# mainMARLIN.net
KiCad netlist of a schematic drawn in Altium Designer
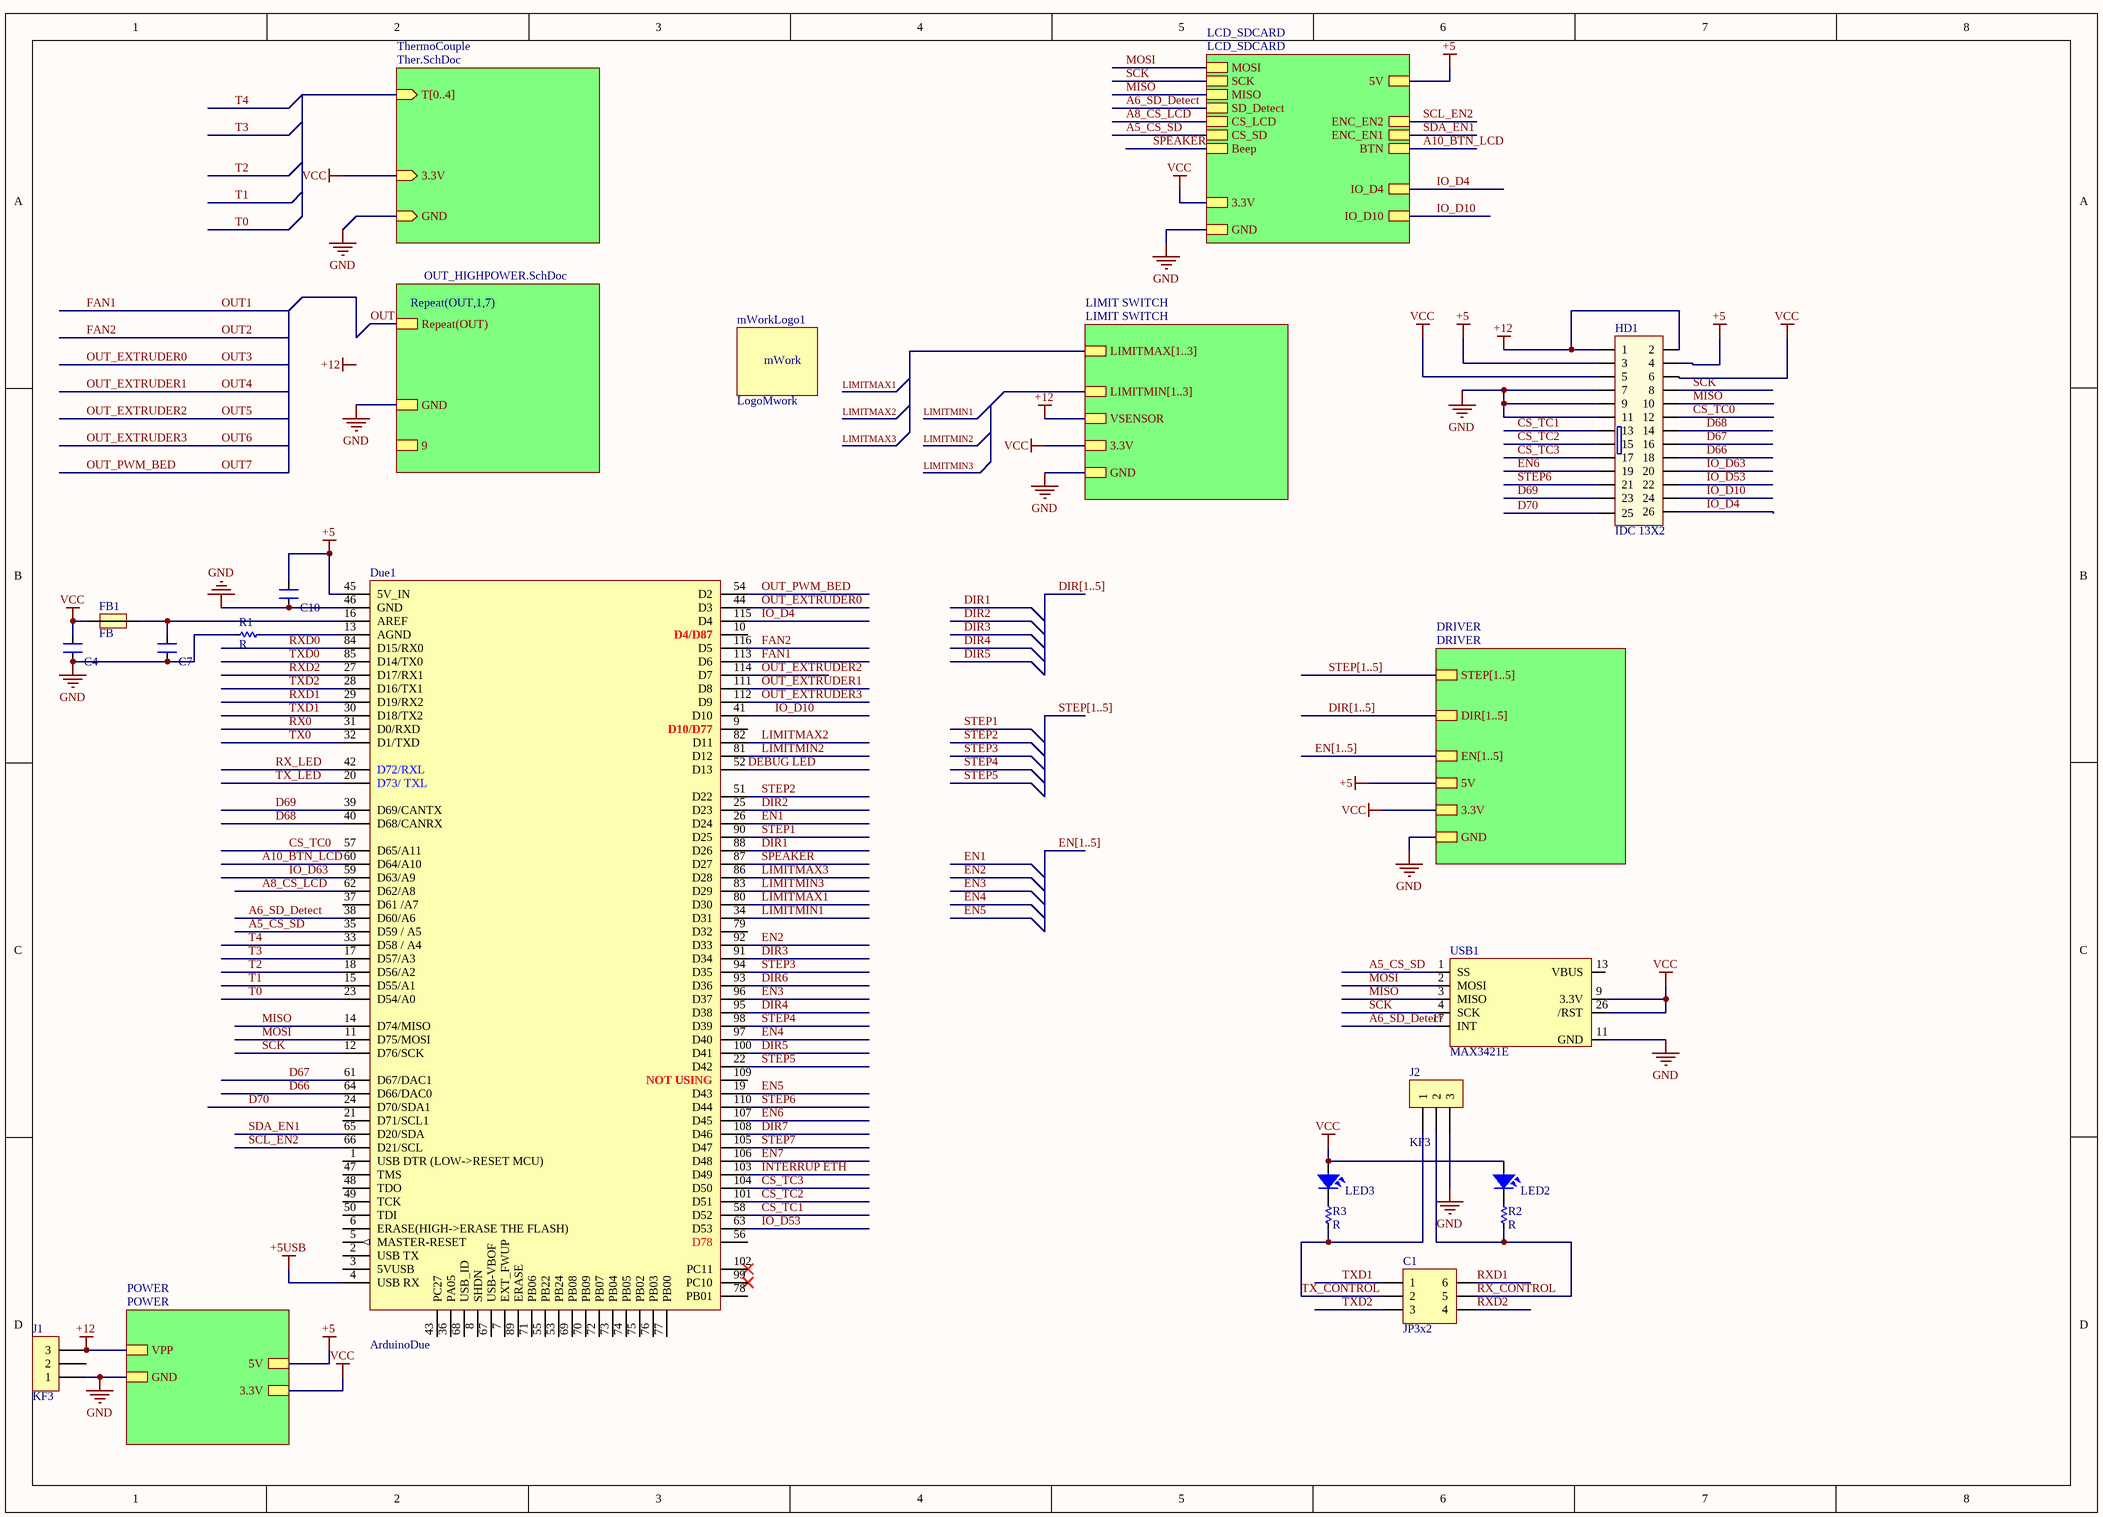
[diagram p0: mainMARLIN.SchDoc]

(export (version "E")
  (design (tool "Eeschema 10.0.6"))
  (components
    (comp (ref "C1")
      (value "JP3x2")
      (footprint "JP3-D2T")
      (description "WR-PHD 2.54 mm Dual Socket Header")
      (fields
        (field (name "MANUFACTURER") "Würth Elektronik eiSos GmbH")
        (field (name "PARTNO") "61300621821")
        (field (name "CREATED BY") "Karrer Zheng")
      )
      (libsource (lib "LIBRARY") (part "JP3x2"))
    )
    (comp (ref "C4") (value "CN") (footprint "CN-SMD-0603_big") (libsource (lib "nhan") (part "CN")))
    (comp (ref "C7") (value "CN") (footprint "CN-SMD-0603_big") (libsource (lib "nhan") (part "CN")))
    (comp (ref "C10") (value "CN") (footprint "CN-SMD-0603_big") (libsource (lib "nhan") (part "CN")))
    (comp (ref "Due1")
      (value "ArduinoDue")
      (footprint "DUE_MODULE_SMT")
      (libsource (lib "nhan") (part "ArduinoDue"))
    )
    (comp (ref "FB1") (value "FB") (footprint "Capacitor_805") (libsource (lib "nhan") (part "FB")))
    (comp (ref "HD1")
      (value "IDC 13X2")
      (footprint "IDC26-B")
      (description "IDC 13x2")
      (libsource (lib "BanLinhKien") (part "IDC 13X2"))
    )
    (comp (ref "J1")
      (value "KF3")
      (footprint "KF3-5.08T")
      (fields
        (field (name "MANUFACTURER") "Würth Elektronik eiSos GmbH")
        (field (name "PARTNO") "691103110003")
        (field (name "CREATED BY") "Karrer Zheng")
      )
      (libsource (lib "BanLinhKien") (part "KF3"))
    )
    (comp (ref "J2")
      (value "KF3")
      (footprint "KF3-5.08T")
      (fields
        (field (name "MANUFACTURER") "Würth Elektronik eiSos GmbH")
        (field (name "PARTNO") "691103110003")
        (field (name "CREATED BY") "Karrer Zheng")
      )
      (libsource (lib "LIBRARY") (part "KF3"))
    )
    (comp (ref "LED2") (value "LED") (footprint "LED-0805-Blue") (libsource (lib "LIBRARY") (part "LED SMD")))
    (comp (ref "LED3") (value "LED") (footprint "LED-0805-Blue") (libsource (lib "LIBRARY") (part "LED SMD")))
    (comp (ref "mWorkLogo1")
      (value "LogoMwork")
      (footprint "LogoMwork15*6")
      (libsource (lib "nhan") (part "LogoMwork"))
    )
    (comp (ref "R1") (value "R") (footprint "RES-SMD-0603_BIG") (libsource (lib "nhan") (part "R")))
    (comp (ref "R2") (value "R") (footprint "RES-SMD-0603_BIG") (libsource (lib "nhan") (part "R")))
    (comp (ref "R3") (value "R") (footprint "RES-SMD-0603_BIG") (libsource (lib "nhan") (part "R")))
    (comp (ref "USB1")
      (value "MAX3421E")
      (footprint "USB_SHIELD")
      (libsource (lib "nhan") (part "USB_Shield_MAX3421E"))
    )
  )
  (nets
    (net (code "1") (name "+5") (class "Default")
      (node (ref "C10") (pin "2") (pinfunction "2_2") (pintype "passive"))
      (node (ref "Due1") (pin "45") (pinfunction "5V_IN_45") (pintype "passive"))
      (node (ref "HD1") (pin "3") (pinfunction "3_3") (pintype "passive"))
      (node (ref "HD1") (pin "4") (pinfunction "4_4") (pintype "passive"))
    )
    (net (code "2") (name "+5USB") (class "Default")
      (node (ref "Due1") (pin "4") (pinfunction "USB_RX_4") (pintype "passive"))
    )
    (net (code "3") (name "+12") (class "Default")
      (node (ref "HD1") (pin "1") (pinfunction "1_1") (pintype "passive"))
      (node (ref "HD1") (pin "2") (pinfunction "2_2") (pintype "passive"))
      (node (ref "J1") (pin "3") (pinfunction "3_3") (pintype "passive"))
    )
    (net (code "5") (name "/A5_CS_SD") (class "Default")
      (node (ref "Due1") (pin "35") (pinfunction "D59_/_A5_35") (pintype "passive"))
      (node (ref "USB1") (pin "1") (pinfunction "SS_1") (pintype "passive"))
    )
    (net (code "6") (name "/A6_SD_Detect") (class "Default")
      (node (ref "Due1") (pin "38") (pinfunction "D60/A6_38") (pintype "passive"))
      (node (ref "USB1") (pin "17") (pinfunction "INT_17") (pintype "passive"))
    )
    (net (code "7") (name "/A8_CS_LCD") (class "Default")
      (node (ref "Due1") (pin "62") (pinfunction "D62/A8_62") (pintype "passive"))
    )
    (net (code "8") (name "/A10_BTN_LCD") (class "Default")
      (node (ref "Due1") (pin "60") (pinfunction "D64/A10_60") (pintype "passive"))
    )
    (net (code "9") (name "/CS_TC0") (class "Default")
      (node (ref "Due1") (pin "57") (pinfunction "D65/A11_57") (pintype "passive"))
      (node (ref "HD1") (pin "12") (pinfunction "12_12") (pintype "passive"))
    )
    (net (code "10") (name "/CS_TC1") (class "Default")
      (node (ref "Due1") (pin "58") (pinfunction "D52_58") (pintype "passive"))
      (node (ref "HD1") (pin "13") (pinfunction "13_13") (pintype "passive"))
    )
    (net (code "11") (name "/CS_TC2") (class "Default")
      (node (ref "Due1") (pin "101") (pinfunction "D51_101") (pintype "passive"))
      (node (ref "HD1") (pin "15") (pinfunction "15_15") (pintype "passive"))
    )
    (net (code "12") (name "/CS_TC3") (class "Default")
      (node (ref "Due1") (pin "104") (pinfunction "D50_104") (pintype "passive"))
      (node (ref "HD1") (pin "17") (pinfunction "17_17") (pintype "passive"))
    )
    (net (code "13") (name "/D66") (class "Default")
      (node (ref "Due1") (pin "64") (pinfunction "D66/DAC0_64") (pintype "passive"))
      (node (ref "HD1") (pin "18") (pinfunction "18_18") (pintype "passive"))
    )
    (net (code "14") (name "/D67") (class "Default")
      (node (ref "Due1") (pin "61") (pinfunction "D67/DAC1_61") (pintype "passive"))
      (node (ref "HD1") (pin "16") (pinfunction "16_16") (pintype "passive"))
    )
    (net (code "15") (name "/D68") (class "Default")
      (node (ref "Due1") (pin "40") (pinfunction "D68/CANRX_40") (pintype "passive"))
      (node (ref "HD1") (pin "14") (pinfunction "14_14") (pintype "passive"))
    )
    (net (code "16") (name "/D69") (class "Default")
      (node (ref "Due1") (pin "39") (pinfunction "D69/CANTX_39") (pintype "passive"))
      (node (ref "HD1") (pin "23") (pinfunction "23_23") (pintype "passive"))
    )
    (net (code "17") (name "/D70") (class "Default")
      (node (ref "Due1") (pin "24") (pinfunction "D70/SDA1_24") (pintype "passive"))
      (node (ref "HD1") (pin "25") (pinfunction "25_25") (pintype "passive"))
    )
    (net (code "18") (name "/DEBUG LED") (class "Default")
      (node (ref "Due1") (pin "52") (pinfunction "D13_52") (pintype "passive"))
    )
    (net (code "19") (name "/DIR1") (class "Default")
      (node (ref "Due1") (pin "88") (pinfunction "D26_88") (pintype "passive"))
    )
    (net (code "20") (name "/DIR2") (class "Default")
      (node (ref "Due1") (pin "25") (pinfunction "D23_25") (pintype "passive"))
    )
    (net (code "21") (name "/DIR3") (class "Default")
      (node (ref "Due1") (pin "91") (pinfunction "D34_91") (pintype "passive"))
    )
    (net (code "22") (name "/DIR4") (class "Default")
      (node (ref "Due1") (pin "95") (pinfunction "D38_95") (pintype "passive"))
    )
    (net (code "23") (name "/DIR5") (class "Default")
      (node (ref "Due1") (pin "100") (pinfunction "D41_100") (pintype "passive"))
    )
    (net (code "24") (name "/DIR6") (class "Default")
      (node (ref "Due1") (pin "93") (pinfunction "D36_93") (pintype "passive"))
    )
    (net (code "25") (name "/DIR7") (class "Default")
      (node (ref "Due1") (pin "108") (pinfunction "D46_108") (pintype "passive"))
    )
    (net (code "27") (name "/EN1") (class "Default")
      (node (ref "Due1") (pin "26") (pinfunction "D24_26") (pintype "passive"))
    )
    (net (code "28") (name "/EN2") (class "Default")
      (node (ref "Due1") (pin "92") (pinfunction "D33_92") (pintype "passive"))
    )
    (net (code "29") (name "/EN3") (class "Default")
      (node (ref "Due1") (pin "96") (pinfunction "D37_96") (pintype "passive"))
    )
    (net (code "30") (name "/EN4") (class "Default")
      (node (ref "Due1") (pin "97") (pinfunction "D40_97") (pintype "passive"))
    )
    (net (code "31") (name "/EN5") (class "Default")
      (node (ref "Due1") (pin "19") (pinfunction "D43_19") (pintype "passive"))
    )
    (net (code "32") (name "/EN6") (class "Default")
      (node (ref "Due1") (pin "107") (pinfunction "D45_107") (pintype "passive"))
      (node (ref "HD1") (pin "19") (pinfunction "19_19") (pintype "passive"))
    )
    (net (code "33") (name "/EN7") (class "Default")
      (node (ref "Due1") (pin "106") (pinfunction "D48_106") (pintype "passive"))
    )
    (net (code "35") (name "/FAN1") (class "Default")
      (node (ref "Due1") (pin "113") (pinfunction "D6_113") (pintype "passive"))
    )
    (net (code "36") (name "/FAN2") (class "Default")
      (node (ref "Due1") (pin "116") (pinfunction "D5_116") (pintype "passive"))
    )
    (net (code "37") (name "/INTERRUP ETH") (class "Default")
      (node (ref "Due1") (pin "103") (pinfunction "D49_103") (pintype "passive"))
    )
    (net (code "38") (name "/IO_D4") (class "Default")
      (node (ref "Due1") (pin "115") (pinfunction "D4_115") (pintype "passive"))
      (node (ref "HD1") (pin "26") (pinfunction "26_26") (pintype "passive"))
    )
    (net (code "39") (name "/IO_D10") (class "Default")
      (node (ref "Due1") (pin "41") (pinfunction "D10_41") (pintype "passive"))
      (node (ref "HD1") (pin "24") (pinfunction "24_24") (pintype "passive"))
    )
    (net (code "40") (name "/IO_D53") (class "Default")
      (node (ref "Due1") (pin "63") (pinfunction "D53_63") (pintype "passive"))
      (node (ref "HD1") (pin "22") (pinfunction "22_22") (pintype "passive"))
    )
    (net (code "41") (name "/IO_D63") (class "Default")
      (node (ref "Due1") (pin "59") (pinfunction "D63/A9_59") (pintype "passive"))
      (node (ref "HD1") (pin "20") (pinfunction "20_20") (pintype "passive"))
    )
    (net (code "42") (name "/LIMITMAX1") (class "Default")
      (node (ref "Due1") (pin "80") (pinfunction "D30_80") (pintype "passive"))
    )
    (net (code "43") (name "/LIMITMAX2") (class "Default")
      (node (ref "Due1") (pin "82") (pinfunction "D11_82") (pintype "passive"))
    )
    (net (code "44") (name "/LIMITMAX3") (class "Default")
      (node (ref "Due1") (pin "86") (pinfunction "D28_86") (pintype "passive"))
    )
    (net (code "46") (name "/LIMITMIN1") (class "Default")
      (node (ref "Due1") (pin "34") (pinfunction "D31_34") (pintype "passive"))
    )
    (net (code "47") (name "/LIMITMIN2") (class "Default")
      (node (ref "Due1") (pin "81") (pinfunction "D12_81") (pintype "passive"))
    )
    (net (code "48") (name "/LIMITMIN3") (class "Default")
      (node (ref "Due1") (pin "83") (pinfunction "D29_83") (pintype "passive"))
    )
    (net (code "50") (name "/MISO") (class "Default")
      (node (ref "Due1") (pin "14") (pinfunction "D74/MISO_14") (pintype "passive"))
      (node (ref "HD1") (pin "10") (pinfunction "10_10") (pintype "passive"))
      (node (ref "USB1") (pin "3") (pinfunction "MISO_3") (pintype "passive"))
    )
    (net (code "51") (name "/MOSI") (class "Default")
      (node (ref "Due1") (pin "11") (pinfunction "D75/MOSI_11") (pintype "passive"))
      (node (ref "USB1") (pin "2") (pinfunction "MOSI_2") (pintype "passive"))
    )
    (net (code "53") (name "/OUT3") (class "Default")
      (node (ref "Due1") (pin "44") (pinfunction "D3_44") (pintype "passive"))
    )
    (net (code "54") (name "/OUT4") (class "Default")
      (node (ref "Due1") (pin "111") (pinfunction "D8_111") (pintype "passive"))
    )
    (net (code "55") (name "/OUT5") (class "Default")
      (node (ref "Due1") (pin "114") (pinfunction "D7_114") (pintype "passive"))
    )
    (net (code "56") (name "/OUT6") (class "Default")
      (node (ref "Due1") (pin "112") (pinfunction "D9_112") (pintype "passive"))
    )
    (net (code "57") (name "/OUT7") (class "Default")
      (node (ref "Due1") (pin "54") (pinfunction "D2_54") (pintype "passive"))
    )
    (net (code "58") (name "/RX0") (class "Default")
      (node (ref "Due1") (pin "31") (pinfunction "D0/RXD_31") (pintype "passive"))
    )
    (net (code "59") (name "/RXD0") (class "Default")
      (node (ref "Due1") (pin "84") (pinfunction "D15/RX0_84") (pintype "passive"))
    )
    (net (code "60") (name "/RXD1") (class "Default")
      (node (ref "C1") (pin "6") (pinfunction "6_6") (pintype "passive"))
      (node (ref "Due1") (pin "29") (pinfunction "D19/RX2_29") (pintype "passive"))
    )
    (net (code "61") (name "/RXD2") (class "Default")
      (node (ref "C1") (pin "4") (pinfunction "4_4") (pintype "passive"))
      (node (ref "Due1") (pin "27") (pinfunction "D17/RX1_27") (pintype "passive"))
    )
    (net (code "62") (name "/RX_CONTROL") (class "Default")
      (node (ref "C1") (pin "5") (pinfunction "5_5") (pintype "passive"))
      (node (ref "J2") (pin "2") (pinfunction "2_2") (pintype "passive"))
      (node (ref "R2") (pin "1") (pinfunction "1_1") (pintype "passive"))
    )
    (net (code "63") (name "/RX_LED") (class "Default")
      (node (ref "Due1") (pin "42") (pinfunction "D72/RXL_42") (pintype "passive"))
    )
    (net (code "64") (name "/SCK") (class "Default")
      (node (ref "Due1") (pin "12") (pinfunction "D76/SCK_12") (pintype "passive"))
      (node (ref "HD1") (pin "8") (pinfunction "8_8") (pintype "passive"))
      (node (ref "USB1") (pin "4") (pinfunction "SCK_4") (pintype "passive"))
    )
    (net (code "65") (name "/SCL_EN2") (class "Default")
      (node (ref "Due1") (pin "66") (pinfunction "D21/SCL_66") (pintype "passive"))
    )
    (net (code "66") (name "/SDA_EN1") (class "Default")
      (node (ref "Due1") (pin "65") (pinfunction "D20/SDA_65") (pintype "passive"))
    )
    (net (code "67") (name "/SPEAKER") (class "Default")
      (node (ref "Due1") (pin "87") (pinfunction "D27_87") (pintype "passive"))
    )
    (net (code "68") (name "/STEP1") (class "Default")
      (node (ref "Due1") (pin "90") (pinfunction "D25_90") (pintype "passive"))
    )
    (net (code "69") (name "/STEP2") (class "Default")
      (node (ref "Due1") (pin "51") (pinfunction "D22_51") (pintype "passive"))
    )
    (net (code "70") (name "/STEP3") (class "Default")
      (node (ref "Due1") (pin "94") (pinfunction "D35_94") (pintype "passive"))
    )
    (net (code "71") (name "/STEP4") (class "Default")
      (node (ref "Due1") (pin "98") (pinfunction "D39_98") (pintype "passive"))
    )
    (net (code "72") (name "/STEP5") (class "Default")
      (node (ref "Due1") (pin "22") (pinfunction "D42_22") (pintype "passive"))
    )
    (net (code "73") (name "/STEP6") (class "Default")
      (node (ref "Due1") (pin "110") (pinfunction "D44_110") (pintype "passive"))
      (node (ref "HD1") (pin "21") (pinfunction "21_21") (pintype "passive"))
    )
    (net (code "74") (name "/STEP7") (class "Default")
      (node (ref "Due1") (pin "105") (pinfunction "D47_105") (pintype "passive"))
    )
    (net (code "76") (name "/T0") (class "Default")
      (node (ref "Due1") (pin "23") (pinfunction "D54/A0_23") (pintype "passive"))
    )
    (net (code "77") (name "/T1") (class "Default")
      (node (ref "Due1") (pin "15") (pinfunction "D55/A1_15") (pintype "passive"))
    )
    (net (code "78") (name "/T2") (class "Default")
      (node (ref "Due1") (pin "18") (pinfunction "D56/A2_18") (pintype "passive"))
    )
    (net (code "79") (name "/T3") (class "Default")
      (node (ref "Due1") (pin "17") (pinfunction "D57/A3_17") (pintype "passive"))
    )
    (net (code "80") (name "/T4") (class "Default")
      (node (ref "Due1") (pin "33") (pinfunction "D58_/_A4_33") (pintype "passive"))
    )
    (net (code "81") (name "/TX0") (class "Default")
      (node (ref "Due1") (pin "32") (pinfunction "D1/TXD_32") (pintype "passive"))
    )
    (net (code "82") (name "/TXD0") (class "Default")
      (node (ref "Due1") (pin "85") (pinfunction "D14/TX0_85") (pintype "passive"))
    )
    (net (code "83") (name "/TXD1") (class "Default")
      (node (ref "C1") (pin "1") (pinfunction "1_1") (pintype "passive"))
      (node (ref "Due1") (pin "30") (pinfunction "D18/TX2_30") (pintype "passive"))
    )
    (net (code "84") (name "/TXD2") (class "Default")
      (node (ref "C1") (pin "3") (pinfunction "3_3") (pintype "passive"))
      (node (ref "Due1") (pin "28") (pinfunction "D16/TX1_28") (pintype "passive"))
    )
    (net (code "85") (name "/TX_CONTROL") (class "Default")
      (node (ref "C1") (pin "2") (pinfunction "2_2") (pintype "passive"))
      (node (ref "J2") (pin "1") (pinfunction "1_1") (pintype "passive"))
      (node (ref "R3") (pin "1") (pinfunction "1_1") (pintype "passive"))
    )
    (net (code "86") (name "/TX_LED") (class "Default")
      (node (ref "Due1") (pin "20") (pinfunction "D73/_TXL_20") (pintype "passive"))
    )
    (net (code "88") (name "GND") (class "Default")
      (node (ref "C10") (pin "1") (pinfunction "1_1") (pintype "passive"))
      (node (ref "C4") (pin "1") (pinfunction "1_1") (pintype "passive"))
      (node (ref "C7") (pin "1") (pinfunction "1_1") (pintype "passive"))
      (node (ref "Due1") (pin "46") (pinfunction "GND_46") (pintype "passive"))
      (node (ref "HD1") (pin "11") (pinfunction "11_11") (pintype "passive"))
      (node (ref "HD1") (pin "7") (pinfunction "7_7") (pintype "passive"))
      (node (ref "HD1") (pin "9") (pinfunction "9_9") (pintype "passive"))
      (node (ref "J1") (pin "1") (pinfunction "1_1") (pintype "passive"))
      (node (ref "J2") (pin "3") (pinfunction "3_3") (pintype "passive"))
      (node (ref "R1") (pin "2") (pinfunction "2_2") (pintype "passive"))
      (node (ref "USB1") (pin "11") (pinfunction "GND_11") (pintype "passive"))
    )
    (net (code "89") (name "Net-(Due1-AGND)") (class "Default")
      (node (ref "Due1") (pin "13") (pinfunction "AGND_13") (pintype "passive"))
      (node (ref "R1") (pin "1") (pinfunction "1_1") (pintype "passive"))
    )
    (net (code "90") (name "Net-(Due1-AREF)") (class "Default")
      (node (ref "C7") (pin "2") (pinfunction "2_2") (pintype "passive"))
      (node (ref "Due1") (pin "16") (pinfunction "AREF_16") (pintype "passive"))
      (node (ref "FB1") (pin "2") (pinfunction "2_2") (pintype "passive"))
    )
    (net (code "91") (name "Net-(LED2-Pad2)") (class "Default")
      (node (ref "LED2") (pin "2") (pinfunction "2_2") (pintype "passive"))
      (node (ref "R2") (pin "2") (pinfunction "2_2") (pintype "passive"))
    )
    (net (code "92") (name "Net-(LED3-Pad2)") (class "Default")
      (node (ref "LED3") (pin "2") (pinfunction "2_2") (pintype "passive"))
      (node (ref "R3") (pin "2") (pinfunction "2_2") (pintype "passive"))
    )
    (net (code "93") (name "VCC") (class "Default")
      (node (ref "C4") (pin "2") (pinfunction "2_2") (pintype "passive"))
      (node (ref "FB1") (pin "1") (pinfunction "1_1") (pintype "passive"))
      (node (ref "HD1") (pin "5") (pinfunction "5_5") (pintype "passive"))
      (node (ref "HD1") (pin "6") (pinfunction "6_6") (pintype "passive"))
      (node (ref "LED2") (pin "1") (pinfunction "1_1") (pintype "passive"))
      (node (ref "LED3") (pin "1") (pinfunction "1_1") (pintype "passive"))
      (node (ref "USB1") (pin "26") (pinfunction "/RST_26") (pintype "passive"))
      (node (ref "USB1") (pin "9") (pinfunction "3.3V_9") (pintype "passive"))
    )
    (net (code "94") (name "unconnected-(Due1-5VUSB-Pad3)") (class "Default")
      (node (ref "Due1") (pin "3") (pinfunction "5VUSB_3") (pintype "passive"))
    )
    (net (code "95") (name "unconnected-(Due1-D4{slash}D87-Pad10)") (class "Default")
      (node (ref "Due1") (pin "10") (pinfunction "D4/D87_10") (pintype "passive"))
    )
    (net (code "96") (name "unconnected-(Due1-D10{slash}D77-Pad9)") (class "Default")
      (node (ref "Due1") (pin "9") (pinfunction "D10/D77_9") (pintype "passive"))
    )
    (net (code "97") (name "unconnected-(Due1-D32-Pad79)") (class "Default")
      (node (ref "Due1") (pin "79") (pinfunction "D32_79") (pintype "passive"))
    )
    (net (code "98") (name "unconnected-(Due1-D61_{slash}A7-Pad37)") (class "Default")
      (node (ref "Due1") (pin "37") (pinfunction "D61_/A7_37") (pintype "passive"))
    )
    (net (code "99") (name "unconnected-(Due1-D71{slash}SCL1-Pad21)") (class "Default")
      (node (ref "Due1") (pin "21") (pinfunction "D71/SCL1_21") (pintype "passive"))
    )
    (net (code "100") (name "unconnected-(Due1-D78-Pad56)") (class "Default")
      (node (ref "Due1") (pin "56") (pinfunction "D78_56") (pintype "passive"))
    )
    (net (code "101") (name "unconnected-(Due1-ERASE(HIGH->ERASE_THE_FLASH)-Pad6)") (class "Default")
      (node (ref "Due1") (pin "6") (pinfunction "ERASE(HIGH->ERASE_THE_FLASH)_6") (pintype "passive"))
    )
    (net (code "102") (name "unconnected-(Due1-ERASE-Pad89)") (class "Default")
      (node (ref "Due1") (pin "89") (pinfunction "ERASE_89") (pintype "passive"))
    )
    (net (code "103") (name "unconnected-(Due1-EXT_FWUP-Pad7)") (class "Default")
      (node (ref "Due1") (pin "7") (pinfunction "EXT_FWUP_7") (pintype "passive"))
    )
    (net (code "104") (name "unconnected-(Due1-MASTER-RESET-Pad5)") (class "Default")
      (node (ref "Due1") (pin "5") (pinfunction "MASTER-RESET_5") (pintype "output"))
    )
    (net (code "105") (name "unconnected-(Due1-NOT_USING-Pad109)") (class "Default")
      (node (ref "Due1") (pin "109") (pinfunction "NOT_USING_109") (pintype "passive"))
    )
    (net (code "106") (name "unconnected-(Due1-PA05-Pad36)") (class "Default")
      (node (ref "Due1") (pin "36") (pinfunction "PA05_36") (pintype "passive"))
    )
    (net (code "107") (name "unconnected-(Due1-PB00-Pad77)") (class "Default")
      (node (ref "Due1") (pin "77") (pinfunction "PB00_77") (pintype "passive"))
    )
    (net (code "108") (name "unconnected-(Due1-PB01-Pad78)") (class "Default")
      (node (ref "Due1") (pin "78") (pinfunction "PB01_78") (pintype "passive"))
    )
    (net (code "109") (name "unconnected-(Due1-PB02-Pad75)") (class "Default")
      (node (ref "Due1") (pin "75") (pinfunction "PB02_75") (pintype "passive"))
    )
    (net (code "110") (name "unconnected-(Due1-PB03-Pad76)") (class "Default")
      (node (ref "Due1") (pin "76") (pinfunction "PB03_76") (pintype "passive"))
    )
    (net (code "111") (name "unconnected-(Due1-PB04-Pad73)") (class "Default")
      (node (ref "Due1") (pin "73") (pinfunction "PB04_73") (pintype "passive"))
    )
    (net (code "112") (name "unconnected-(Due1-PB05-Pad74)") (class "Default")
      (node (ref "Due1") (pin "74") (pinfunction "PB05_74") (pintype "passive"))
    )
    (net (code "113") (name "unconnected-(Due1-PB06-Pad71)") (class "Default")
      (node (ref "Due1") (pin "71") (pinfunction "PB06_71") (pintype "passive"))
    )
    (net (code "114") (name "unconnected-(Due1-PB07-Pad72)") (class "Default")
      (node (ref "Due1") (pin "72") (pinfunction "PB07_72") (pintype "passive"))
    )
    (net (code "115") (name "unconnected-(Due1-PB08-Pad69)") (class "Default")
      (node (ref "Due1") (pin "69") (pinfunction "PB08_69") (pintype "passive"))
    )
    (net (code "116") (name "unconnected-(Due1-PB09-Pad70)") (class "Default")
      (node (ref "Due1") (pin "70") (pinfunction "PB09_70") (pintype "passive"))
    )
    (net (code "117") (name "unconnected-(Due1-PB22-Pad55)") (class "Default")
      (node (ref "Due1") (pin "55") (pinfunction "PB22_55") (pintype "passive"))
    )
    (net (code "118") (name "unconnected-(Due1-PB24-Pad53)") (class "Default")
      (node (ref "Due1") (pin "53") (pinfunction "PB24_53") (pintype "passive"))
    )
    (net (code "119") (name "unconnected-(Due1-PC10-Pad99)") (class "Default")
      (node (ref "Due1") (pin "99") (pinfunction "PC10_99") (pintype "passive+no_connect"))
    )
    (net (code "120") (name "unconnected-(Due1-PC11-Pad102)") (class "Default")
      (node (ref "Due1") (pin "102") (pinfunction "PC11_102") (pintype "passive+no_connect"))
    )
    (net (code "121") (name "unconnected-(Due1-PC27-Pad43)") (class "Default")
      (node (ref "Due1") (pin "43") (pinfunction "PC27_43") (pintype "passive"))
    )
    (net (code "122") (name "unconnected-(Due1-SHDN-Pad8)") (class "Default")
      (node (ref "Due1") (pin "8") (pinfunction "SHDN_8") (pintype "passive"))
    )
    (net (code "123") (name "unconnected-(Due1-TCK-Pad49)") (class "Default")
      (node (ref "Due1") (pin "49") (pinfunction "TCK_49") (pintype "passive"))
    )
    (net (code "124") (name "unconnected-(Due1-TDI-Pad50)") (class "Default")
      (node (ref "Due1") (pin "50") (pinfunction "TDI_50") (pintype "passive"))
    )
    (net (code "125") (name "unconnected-(Due1-TDO-Pad48)") (class "Default")
      (node (ref "Due1") (pin "48") (pinfunction "TDO_48") (pintype "passive"))
    )
    (net (code "126") (name "unconnected-(Due1-TMS-Pad47)") (class "Default")
      (node (ref "Due1") (pin "47") (pinfunction "TMS_47") (pintype "passive"))
    )
    (net (code "127") (name "unconnected-(Due1-USB-VBOF-Pad67)") (class "Default")
      (node (ref "Due1") (pin "67") (pinfunction "USB-VBOF_67") (pintype "passive"))
    )
    (net (code "128") (name "unconnected-(Due1-USB_DTR_(LOW->RESET_MCU)-Pad1)") (class "Default")
      (node (ref "Due1") (pin "1") (pinfunction "USB_DTR_(LOW->RESET_MCU)_1") (pintype "passive"))
    )
    (net (code "129") (name "unconnected-(Due1-USB_ID-Pad68)") (class "Default")
      (node (ref "Due1") (pin "68") (pinfunction "USB_ID_68") (pintype "passive"))
    )
    (net (code "130") (name "unconnected-(Due1-USB_TX-Pad2)") (class "Default")
      (node (ref "Due1") (pin "2") (pinfunction "USB_TX_2") (pintype "passive"))
    )
    (net (code "131") (name "unconnected-(J1-Pad2)") (class "Default")
      (node (ref "J1") (pin "2") (pinfunction "2_2") (pintype "passive"))
    )
    (net (code "132") (name "unconnected-(USB1-VBUS-Pad13)") (class "Default")
      (node (ref "USB1") (pin "13") (pinfunction "VBUS_13") (pintype "passive"))
    )
  )
)
